# picotouch_grid.net
KiCad netlist of a schematic drawn in EAGLE
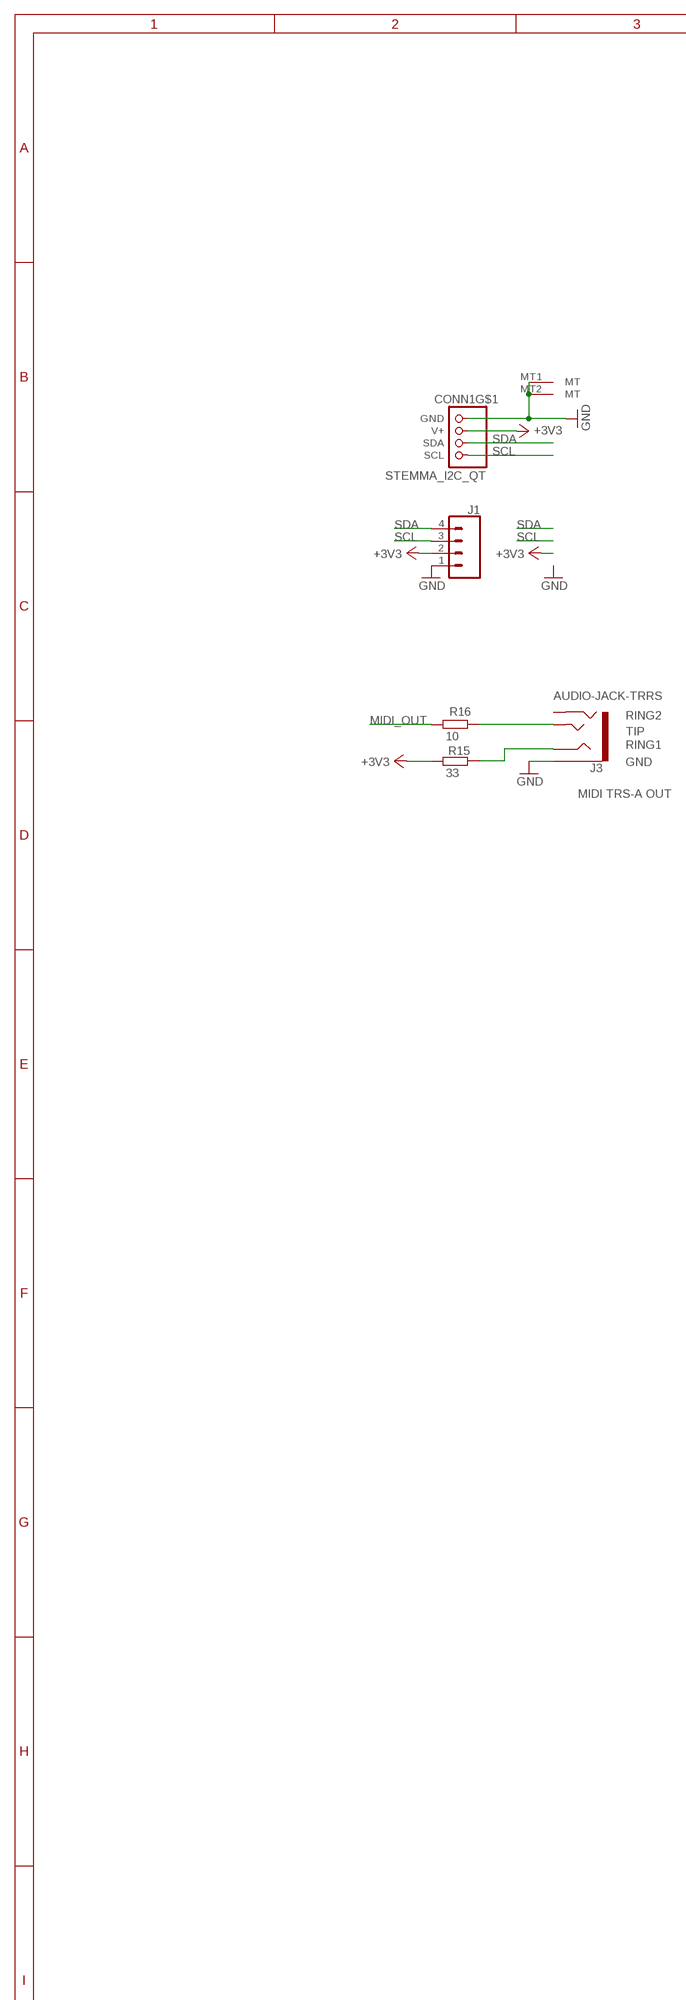
[diagram p0: schematic, sheet 1, part 1 of 2]
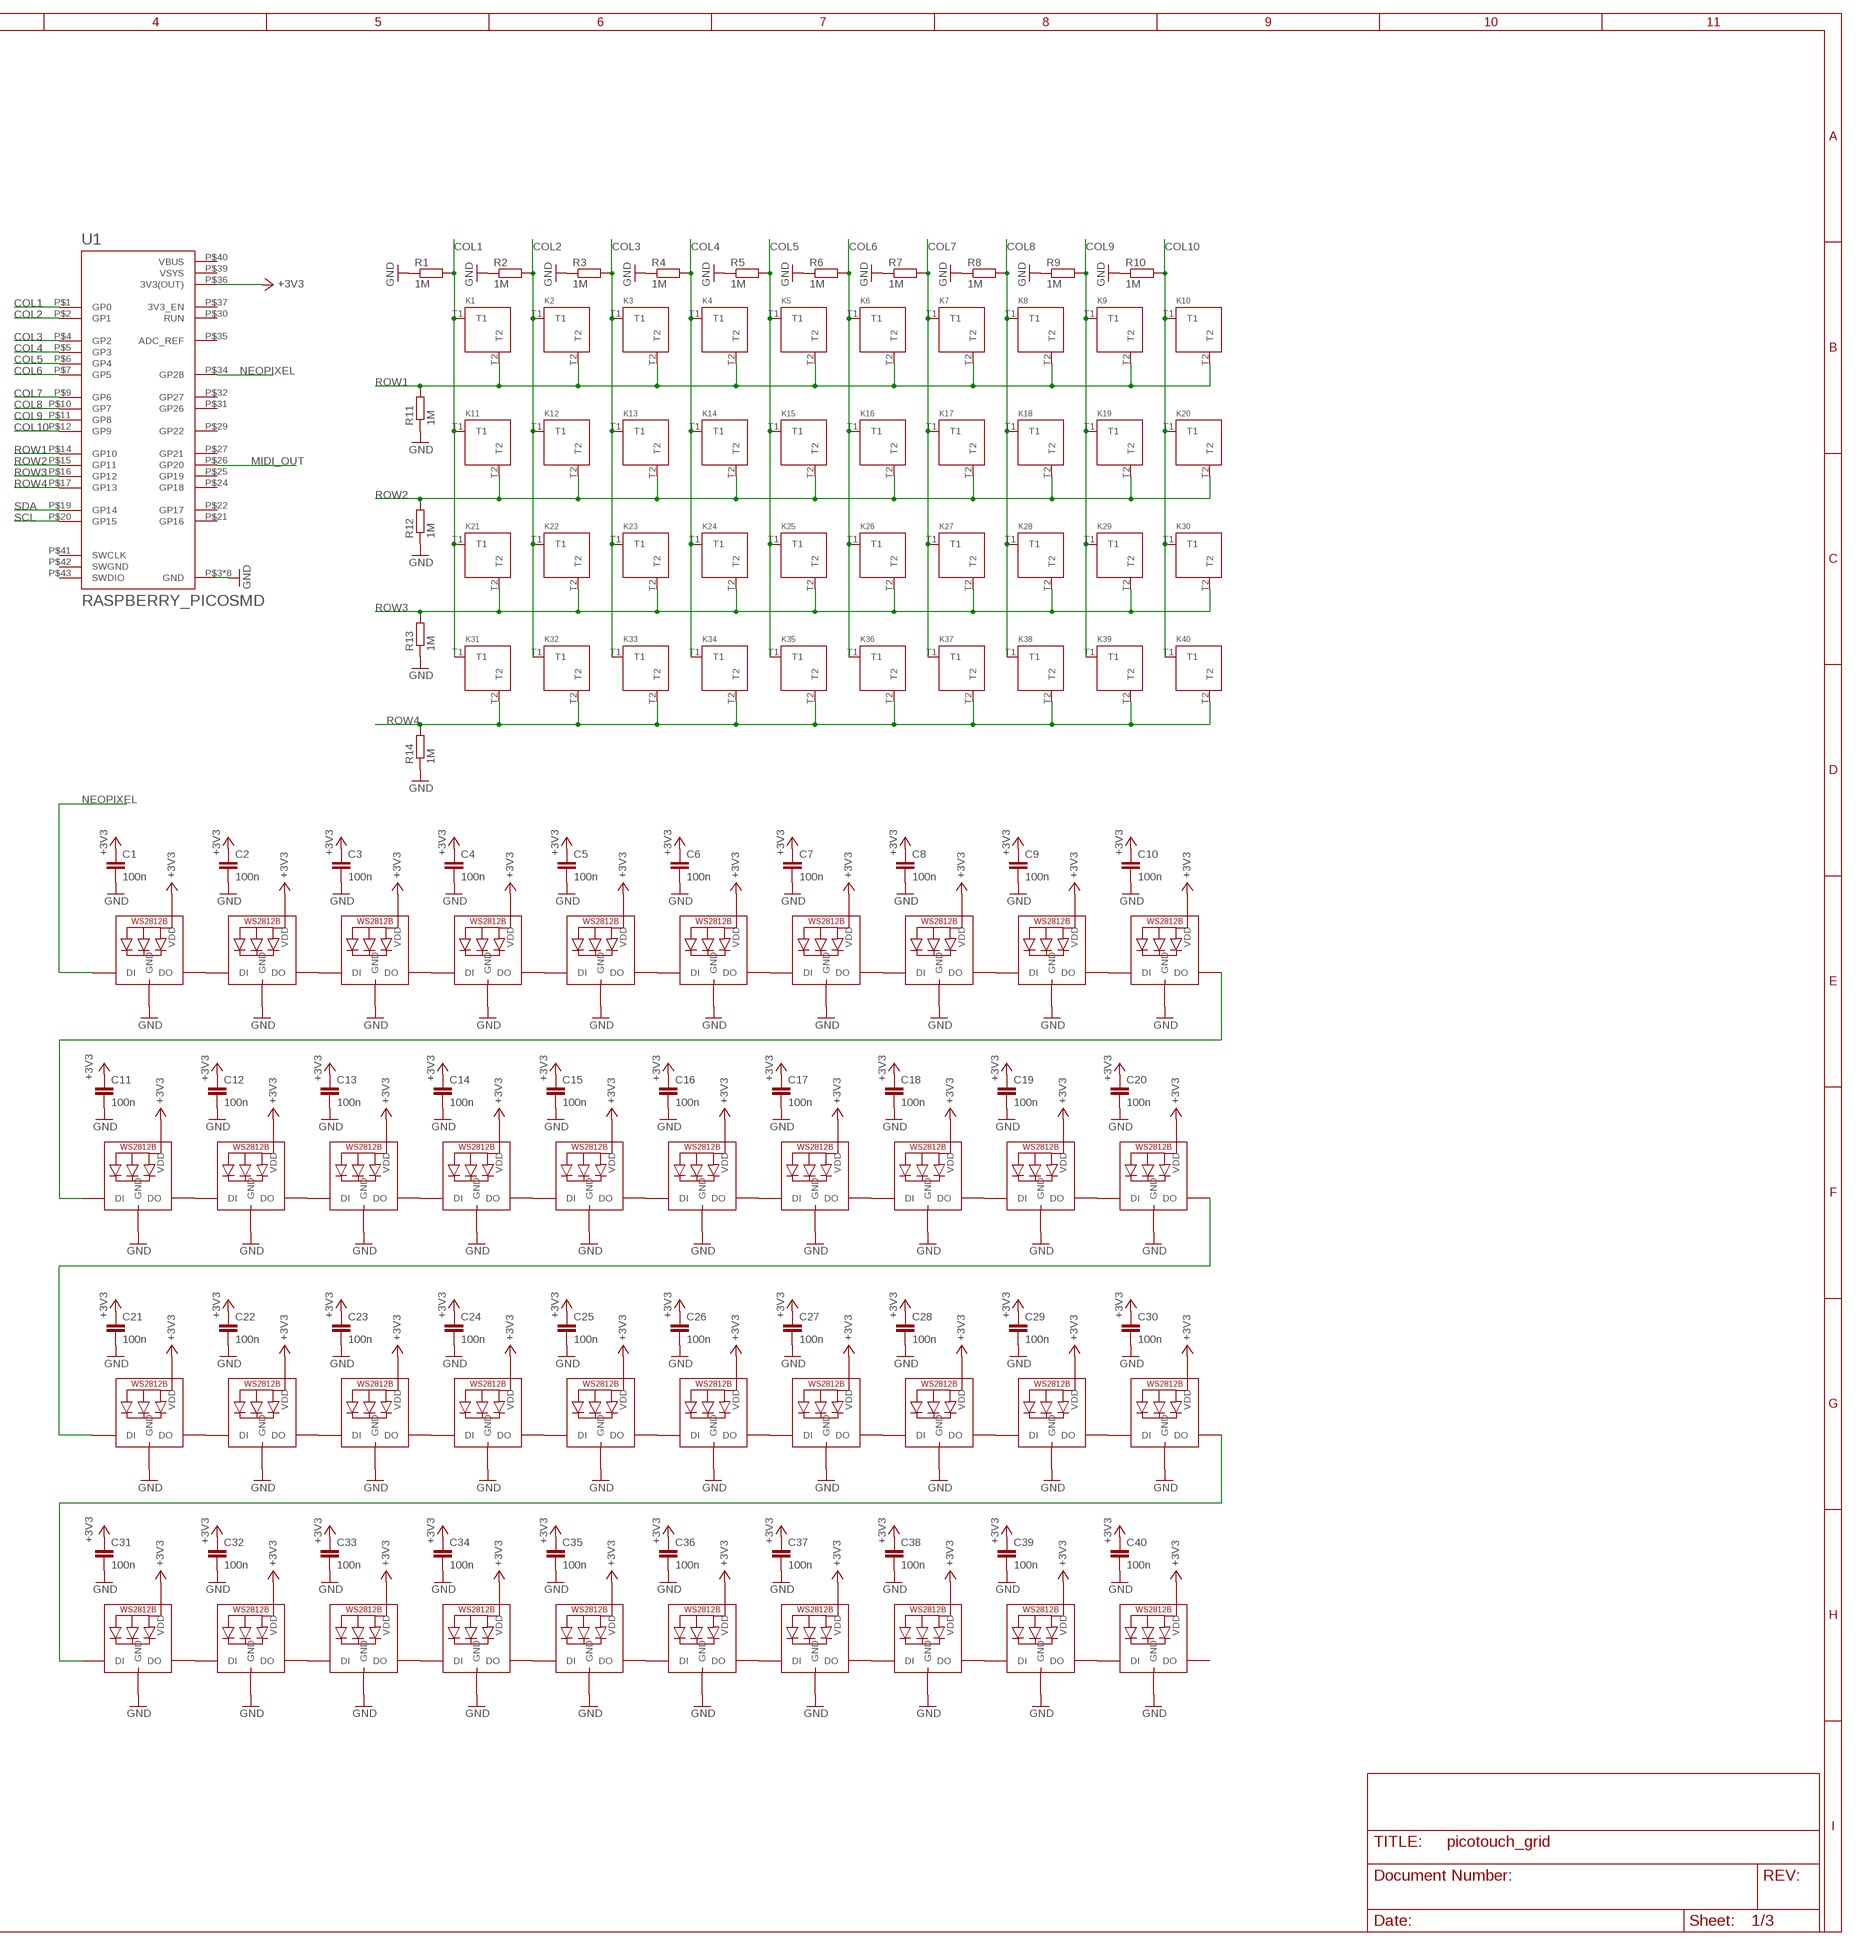
[diagram p1: schematic, sheet 1, part 2 of 2]

(export (version "E")
  (design (tool "Eeschema 10.0.6"))
  (components
    (comp (ref "C1")
      (value "100n")
      (footprint "eagle-import:C0805")
      (libsource (lib "eagle-import") (part "C-EUC0805"))
    )
    (comp (ref "C2")
      (value "100n")
      (footprint "eagle-import:C0805")
      (libsource (lib "eagle-import") (part "C-EUC0805"))
    )
    (comp (ref "C3")
      (value "100n")
      (footprint "eagle-import:C0805")
      (libsource (lib "eagle-import") (part "C-EUC0805"))
    )
    (comp (ref "C4")
      (value "100n")
      (footprint "eagle-import:C0805")
      (libsource (lib "eagle-import") (part "C-EUC0805"))
    )
    (comp (ref "C5")
      (value "100n")
      (footprint "eagle-import:C0805")
      (libsource (lib "eagle-import") (part "C-EUC0805"))
    )
    (comp (ref "C6")
      (value "100n")
      (footprint "eagle-import:C0805")
      (libsource (lib "eagle-import") (part "C-EUC0805"))
    )
    (comp (ref "C7")
      (value "100n")
      (footprint "eagle-import:C0805")
      (libsource (lib "eagle-import") (part "C-EUC0805"))
    )
    (comp (ref "C8")
      (value "100n")
      (footprint "eagle-import:C0805")
      (libsource (lib "eagle-import") (part "C-EUC0805"))
    )
    (comp (ref "C9")
      (value "100n")
      (footprint "eagle-import:C0805")
      (libsource (lib "eagle-import") (part "C-EUC0805"))
    )
    (comp (ref "C10")
      (value "100n")
      (footprint "eagle-import:C0805")
      (libsource (lib "eagle-import") (part "C-EUC0805"))
    )
    (comp (ref "C11")
      (value "100n")
      (footprint "eagle-import:C0805")
      (libsource (lib "eagle-import") (part "C-EUC0805"))
    )
    (comp (ref "C12")
      (value "100n")
      (footprint "eagle-import:C0805")
      (libsource (lib "eagle-import") (part "C-EUC0805"))
    )
    (comp (ref "C13")
      (value "100n")
      (footprint "eagle-import:C0805")
      (libsource (lib "eagle-import") (part "C-EUC0805"))
    )
    (comp (ref "C14")
      (value "100n")
      (footprint "eagle-import:C0805")
      (libsource (lib "eagle-import") (part "C-EUC0805"))
    )
    (comp (ref "C15")
      (value "100n")
      (footprint "eagle-import:C0805")
      (libsource (lib "eagle-import") (part "C-EUC0805"))
    )
    (comp (ref "C16")
      (value "100n")
      (footprint "eagle-import:C0805")
      (libsource (lib "eagle-import") (part "C-EUC0805"))
    )
    (comp (ref "C17")
      (value "100n")
      (footprint "eagle-import:C0805")
      (libsource (lib "eagle-import") (part "C-EUC0805"))
    )
    (comp (ref "C18")
      (value "100n")
      (footprint "eagle-import:C0805")
      (libsource (lib "eagle-import") (part "C-EUC0805"))
    )
    (comp (ref "C19")
      (value "100n")
      (footprint "eagle-import:C0805")
      (libsource (lib "eagle-import") (part "C-EUC0805"))
    )
    (comp (ref "C20")
      (value "100n")
      (footprint "eagle-import:C0805")
      (libsource (lib "eagle-import") (part "C-EUC0805"))
    )
    (comp (ref "C21")
      (value "100n")
      (footprint "eagle-import:C0805")
      (libsource (lib "eagle-import") (part "C-EUC0805"))
    )
    (comp (ref "C22")
      (value "100n")
      (footprint "eagle-import:C0805")
      (libsource (lib "eagle-import") (part "C-EUC0805"))
    )
    (comp (ref "C23")
      (value "100n")
      (footprint "eagle-import:C0805")
      (libsource (lib "eagle-import") (part "C-EUC0805"))
    )
    (comp (ref "C24")
      (value "100n")
      (footprint "eagle-import:C0805")
      (libsource (lib "eagle-import") (part "C-EUC0805"))
    )
    (comp (ref "C25")
      (value "100n")
      (footprint "eagle-import:C0805")
      (libsource (lib "eagle-import") (part "C-EUC0805"))
    )
    (comp (ref "C26")
      (value "100n")
      (footprint "eagle-import:C0805")
      (libsource (lib "eagle-import") (part "C-EUC0805"))
    )
    (comp (ref "C27")
      (value "100n")
      (footprint "eagle-import:C0805")
      (libsource (lib "eagle-import") (part "C-EUC0805"))
    )
    (comp (ref "C28")
      (value "100n")
      (footprint "eagle-import:C0805")
      (libsource (lib "eagle-import") (part "C-EUC0805"))
    )
    (comp (ref "C29")
      (value "100n")
      (footprint "eagle-import:C0805")
      (libsource (lib "eagle-import") (part "C-EUC0805"))
    )
    (comp (ref "C30")
      (value "100n")
      (footprint "eagle-import:C0805")
      (libsource (lib "eagle-import") (part "C-EUC0805"))
    )
    (comp (ref "C31")
      (value "100n")
      (footprint "eagle-import:C0805")
      (libsource (lib "eagle-import") (part "C-EUC0805"))
    )
    (comp (ref "C32")
      (value "100n")
      (footprint "eagle-import:C0805")
      (libsource (lib "eagle-import") (part "C-EUC0805"))
    )
    (comp (ref "C33")
      (value "100n")
      (footprint "eagle-import:C0805")
      (libsource (lib "eagle-import") (part "C-EUC0805"))
    )
    (comp (ref "C34")
      (value "100n")
      (footprint "eagle-import:C0805")
      (libsource (lib "eagle-import") (part "C-EUC0805"))
    )
    (comp (ref "C35")
      (value "100n")
      (footprint "eagle-import:C0805")
      (libsource (lib "eagle-import") (part "C-EUC0805"))
    )
    (comp (ref "C36")
      (value "100n")
      (footprint "eagle-import:C0805")
      (libsource (lib "eagle-import") (part "C-EUC0805"))
    )
    (comp (ref "C37")
      (value "100n")
      (footprint "eagle-import:C0805")
      (libsource (lib "eagle-import") (part "C-EUC0805"))
    )
    (comp (ref "C38")
      (value "100n")
      (footprint "eagle-import:C0805")
      (libsource (lib "eagle-import") (part "C-EUC0805"))
    )
    (comp (ref "C39")
      (value "100n")
      (footprint "eagle-import:C0805")
      (libsource (lib "eagle-import") (part "C-EUC0805"))
    )
    (comp (ref "C40")
      (value "100n")
      (footprint "eagle-import:C0805")
      (libsource (lib "eagle-import") (part "C-EUC0805"))
    )
    (comp (ref "CONN1")
      (value "STEMMA_I2C_QT")
      (footprint "eagle-import:JST_SH4")
      (fields
        (field (name "LCSC2") "C160404")
        (field (name "MPN") "HC-1.0-4PWT")
        (field (name "MPN2") "SM04B-SRSS-TB")
      )
      (libsource (lib "eagle-import") (part "STEMMA_I2C_QT"))
    )
    (comp (ref "J1")
      (value "CONN_04")
      (footprint "eagle-import:1X04")
      (libsource (lib "eagle-import") (part "CONN_04"))
    )
    (comp (ref "J3")
      (value "AUDIO-JACK-TRRS")
      (footprint "eagle-import:PJ-320D_SPARKFUN")
      (fields (field (name "MPN") "PJ-320D") (field (name "LCSC") "C431535"))
      (libsource (lib "eagle-import") (part "AUDIO-JACK-TRRS"))
    )
    (comp (ref "K1")
      (value "TOUCHKEYH")
      (footprint "eagle-import:TOUCHPAD_KEY_0.5IN_LEDHOLE")
      (libsource (lib "eagle-import") (part "TOUCHKEYH"))
    )
    (comp (ref "K2")
      (value "TOUCHKEYH")
      (footprint "eagle-import:TOUCHPAD_KEY_0.5IN_LEDHOLE")
      (libsource (lib "eagle-import") (part "TOUCHKEYH"))
    )
    (comp (ref "K3")
      (value "TOUCHKEYH")
      (footprint "eagle-import:TOUCHPAD_KEY_0.5IN_LEDHOLE")
      (libsource (lib "eagle-import") (part "TOUCHKEYH"))
    )
    (comp (ref "K4")
      (value "TOUCHKEYH")
      (footprint "eagle-import:TOUCHPAD_KEY_0.5IN_LEDHOLE")
      (libsource (lib "eagle-import") (part "TOUCHKEYH"))
    )
    (comp (ref "K5")
      (value "TOUCHKEYH")
      (footprint "eagle-import:TOUCHPAD_KEY_0.5IN_LEDHOLE")
      (libsource (lib "eagle-import") (part "TOUCHKEYH"))
    )
    (comp (ref "K6")
      (value "TOUCHKEYH")
      (footprint "eagle-import:TOUCHPAD_KEY_0.5IN_LEDHOLE")
      (libsource (lib "eagle-import") (part "TOUCHKEYH"))
    )
    (comp (ref "K7")
      (value "TOUCHKEYH")
      (footprint "eagle-import:TOUCHPAD_KEY_0.5IN_LEDHOLE")
      (libsource (lib "eagle-import") (part "TOUCHKEYH"))
    )
    (comp (ref "K8")
      (value "TOUCHKEYH")
      (footprint "eagle-import:TOUCHPAD_KEY_0.5IN_LEDHOLE")
      (libsource (lib "eagle-import") (part "TOUCHKEYH"))
    )
    (comp (ref "K9")
      (value "TOUCHKEYH")
      (footprint "eagle-import:TOUCHPAD_KEY_0.5IN_LEDHOLE")
      (libsource (lib "eagle-import") (part "TOUCHKEYH"))
    )
    (comp (ref "K10")
      (value "TOUCHKEYH")
      (footprint "eagle-import:TOUCHPAD_KEY_0.5IN_LEDHOLE")
      (libsource (lib "eagle-import") (part "TOUCHKEYH"))
    )
    (comp (ref "K11")
      (value "TOUCHKEYH")
      (footprint "eagle-import:TOUCHPAD_KEY_0.5IN_LEDHOLE")
      (libsource (lib "eagle-import") (part "TOUCHKEYH"))
    )
    (comp (ref "K12")
      (value "TOUCHKEYH")
      (footprint "eagle-import:TOUCHPAD_KEY_0.5IN_LEDHOLE")
      (libsource (lib "eagle-import") (part "TOUCHKEYH"))
    )
    (comp (ref "K13")
      (value "TOUCHKEYH")
      (footprint "eagle-import:TOUCHPAD_KEY_0.5IN_LEDHOLE")
      (libsource (lib "eagle-import") (part "TOUCHKEYH"))
    )
    (comp (ref "K14")
      (value "TOUCHKEYH")
      (footprint "eagle-import:TOUCHPAD_KEY_0.5IN_LEDHOLE")
      (libsource (lib "eagle-import") (part "TOUCHKEYH"))
    )
    (comp (ref "K15")
      (value "TOUCHKEYH")
      (footprint "eagle-import:TOUCHPAD_KEY_0.5IN_LEDHOLE")
      (libsource (lib "eagle-import") (part "TOUCHKEYH"))
    )
    (comp (ref "K16")
      (value "TOUCHKEYH")
      (footprint "eagle-import:TOUCHPAD_KEY_0.5IN_LEDHOLE")
      (libsource (lib "eagle-import") (part "TOUCHKEYH"))
    )
    (comp (ref "K17")
      (value "TOUCHKEYH")
      (footprint "eagle-import:TOUCHPAD_KEY_0.5IN_LEDHOLE")
      (libsource (lib "eagle-import") (part "TOUCHKEYH"))
    )
    (comp (ref "K18")
      (value "TOUCHKEYH")
      (footprint "eagle-import:TOUCHPAD_KEY_0.5IN_LEDHOLE")
      (libsource (lib "eagle-import") (part "TOUCHKEYH"))
    )
    (comp (ref "K19")
      (value "TOUCHKEYH")
      (footprint "eagle-import:TOUCHPAD_KEY_0.5IN_LEDHOLE")
      (libsource (lib "eagle-import") (part "TOUCHKEYH"))
    )
    (comp (ref "K20")
      (value "TOUCHKEYH")
      (footprint "eagle-import:TOUCHPAD_KEY_0.5IN_LEDHOLE")
      (libsource (lib "eagle-import") (part "TOUCHKEYH"))
    )
    (comp (ref "K21")
      (value "TOUCHKEYH")
      (footprint "eagle-import:TOUCHPAD_KEY_0.5IN_LEDHOLE")
      (libsource (lib "eagle-import") (part "TOUCHKEYH"))
    )
    (comp (ref "K22")
      (value "TOUCHKEYH")
      (footprint "eagle-import:TOUCHPAD_KEY_0.5IN_LEDHOLE")
      (libsource (lib "eagle-import") (part "TOUCHKEYH"))
    )
    (comp (ref "K23")
      (value "TOUCHKEYH")
      (footprint "eagle-import:TOUCHPAD_KEY_0.5IN_LEDHOLE")
      (libsource (lib "eagle-import") (part "TOUCHKEYH"))
    )
    (comp (ref "K24")
      (value "TOUCHKEYH")
      (footprint "eagle-import:TOUCHPAD_KEY_0.5IN_LEDHOLE")
      (libsource (lib "eagle-import") (part "TOUCHKEYH"))
    )
    (comp (ref "K25")
      (value "TOUCHKEYH")
      (footprint "eagle-import:TOUCHPAD_KEY_0.5IN_LEDHOLE")
      (libsource (lib "eagle-import") (part "TOUCHKEYH"))
    )
    (comp (ref "K26")
      (value "TOUCHKEYH")
      (footprint "eagle-import:TOUCHPAD_KEY_0.5IN_LEDHOLE")
      (libsource (lib "eagle-import") (part "TOUCHKEYH"))
    )
    (comp (ref "K27")
      (value "TOUCHKEYH")
      (footprint "eagle-import:TOUCHPAD_KEY_0.5IN_LEDHOLE")
      (libsource (lib "eagle-import") (part "TOUCHKEYH"))
    )
    (comp (ref "K28")
      (value "TOUCHKEYH")
      (footprint "eagle-import:TOUCHPAD_KEY_0.5IN_LEDHOLE")
      (libsource (lib "eagle-import") (part "TOUCHKEYH"))
    )
    (comp (ref "K29")
      (value "TOUCHKEYH")
      (footprint "eagle-import:TOUCHPAD_KEY_0.5IN_LEDHOLE")
      (libsource (lib "eagle-import") (part "TOUCHKEYH"))
    )
    (comp (ref "K30")
      (value "TOUCHKEYH")
      (footprint "eagle-import:TOUCHPAD_KEY_0.5IN_LEDHOLE")
      (libsource (lib "eagle-import") (part "TOUCHKEYH"))
    )
    (comp (ref "K31")
      (value "TOUCHKEYH")
      (footprint "eagle-import:TOUCHPAD_KEY_0.5IN_LEDHOLE")
      (libsource (lib "eagle-import") (part "TOUCHKEYH"))
    )
    (comp (ref "K32")
      (value "TOUCHKEYH")
      (footprint "eagle-import:TOUCHPAD_KEY_0.5IN_LEDHOLE")
      (libsource (lib "eagle-import") (part "TOUCHKEYH"))
    )
    (comp (ref "K33")
      (value "TOUCHKEYH")
      (footprint "eagle-import:TOUCHPAD_KEY_0.5IN_LEDHOLE")
      (libsource (lib "eagle-import") (part "TOUCHKEYH"))
    )
    (comp (ref "K34")
      (value "TOUCHKEYH")
      (footprint "eagle-import:TOUCHPAD_KEY_0.5IN_LEDHOLE")
      (libsource (lib "eagle-import") (part "TOUCHKEYH"))
    )
    (comp (ref "K35")
      (value "TOUCHKEYH")
      (footprint "eagle-import:TOUCHPAD_KEY_0.5IN_LEDHOLE")
      (libsource (lib "eagle-import") (part "TOUCHKEYH"))
    )
    (comp (ref "K36")
      (value "TOUCHKEYH")
      (footprint "eagle-import:TOUCHPAD_KEY_0.5IN_LEDHOLE")
      (libsource (lib "eagle-import") (part "TOUCHKEYH"))
    )
    (comp (ref "K37")
      (value "TOUCHKEYH")
      (footprint "eagle-import:TOUCHPAD_KEY_0.5IN_LEDHOLE")
      (libsource (lib "eagle-import") (part "TOUCHKEYH"))
    )
    (comp (ref "K38")
      (value "TOUCHKEYH")
      (footprint "eagle-import:TOUCHPAD_KEY_0.5IN_LEDHOLE")
      (libsource (lib "eagle-import") (part "TOUCHKEYH"))
    )
    (comp (ref "K39")
      (value "TOUCHKEYH")
      (footprint "eagle-import:TOUCHPAD_KEY_0.5IN_LEDHOLE")
      (libsource (lib "eagle-import") (part "TOUCHKEYH"))
    )
    (comp (ref "K40")
      (value "TOUCHKEYH")
      (footprint "eagle-import:TOUCHPAD_KEY_0.5IN_LEDHOLE")
      (libsource (lib "eagle-import") (part "TOUCHKEYH"))
    )
    (comp (ref "LED1")
      (value "MICROBUILDER_WS2812B_SK6812E")
      (footprint "eagle-import:MICROBUILDER_NEO3535_REVERSE")
      (libsource (lib "eagle-import") (part "MICROBUILDER_WS2812B_SK6812E"))
    )
    (comp (ref "LED2")
      (value "MICROBUILDER_WS2812B_SK6812E")
      (footprint "eagle-import:MICROBUILDER_NEO3535_REVERSE")
      (libsource (lib "eagle-import") (part "MICROBUILDER_WS2812B_SK6812E"))
    )
    (comp (ref "LED3")
      (value "MICROBUILDER_WS2812B_SK6812E")
      (footprint "eagle-import:MICROBUILDER_NEO3535_REVERSE")
      (libsource (lib "eagle-import") (part "MICROBUILDER_WS2812B_SK6812E"))
    )
    (comp (ref "LED4")
      (value "MICROBUILDER_WS2812B_SK6812E")
      (footprint "eagle-import:MICROBUILDER_NEO3535_REVERSE")
      (libsource (lib "eagle-import") (part "MICROBUILDER_WS2812B_SK6812E"))
    )
    (comp (ref "LED5")
      (value "MICROBUILDER_WS2812B_SK6812E")
      (footprint "eagle-import:MICROBUILDER_NEO3535_REVERSE")
      (libsource (lib "eagle-import") (part "MICROBUILDER_WS2812B_SK6812E"))
    )
    (comp (ref "LED6")
      (value "MICROBUILDER_WS2812B_SK6812E")
      (footprint "eagle-import:MICROBUILDER_NEO3535_REVERSE")
      (libsource (lib "eagle-import") (part "MICROBUILDER_WS2812B_SK6812E"))
    )
    (comp (ref "LED7")
      (value "MICROBUILDER_WS2812B_SK6812E")
      (footprint "eagle-import:MICROBUILDER_NEO3535_REVERSE")
      (libsource (lib "eagle-import") (part "MICROBUILDER_WS2812B_SK6812E"))
    )
    (comp (ref "LED8")
      (value "MICROBUILDER_WS2812B_SK6812E")
      (footprint "eagle-import:MICROBUILDER_NEO3535_REVERSE")
      (libsource (lib "eagle-import") (part "MICROBUILDER_WS2812B_SK6812E"))
    )
    (comp (ref "LED9")
      (value "MICROBUILDER_WS2812B_SK6812E")
      (footprint "eagle-import:MICROBUILDER_NEO3535_REVERSE")
      (libsource (lib "eagle-import") (part "MICROBUILDER_WS2812B_SK6812E"))
    )
    (comp (ref "LED10")
      (value "MICROBUILDER_WS2812B_SK6812E")
      (footprint "eagle-import:MICROBUILDER_NEO3535_REVERSE")
      (libsource (lib "eagle-import") (part "MICROBUILDER_WS2812B_SK6812E"))
    )
    (comp (ref "LED11")
      (value "MICROBUILDER_WS2812B_SK6812E")
      (footprint "eagle-import:MICROBUILDER_NEO3535_REVERSE")
      (libsource (lib "eagle-import") (part "MICROBUILDER_WS2812B_SK6812E"))
    )
    (comp (ref "LED12")
      (value "MICROBUILDER_WS2812B_SK6812E")
      (footprint "eagle-import:MICROBUILDER_NEO3535_REVERSE")
      (libsource (lib "eagle-import") (part "MICROBUILDER_WS2812B_SK6812E"))
    )
    (comp (ref "LED13")
      (value "MICROBUILDER_WS2812B_SK6812E")
      (footprint "eagle-import:MICROBUILDER_NEO3535_REVERSE")
      (libsource (lib "eagle-import") (part "MICROBUILDER_WS2812B_SK6812E"))
    )
    (comp (ref "LED14")
      (value "MICROBUILDER_WS2812B_SK6812E")
      (footprint "eagle-import:MICROBUILDER_NEO3535_REVERSE")
      (libsource (lib "eagle-import") (part "MICROBUILDER_WS2812B_SK6812E"))
    )
    (comp (ref "LED15")
      (value "MICROBUILDER_WS2812B_SK6812E")
      (footprint "eagle-import:MICROBUILDER_NEO3535_REVERSE")
      (libsource (lib "eagle-import") (part "MICROBUILDER_WS2812B_SK6812E"))
    )
    (comp (ref "LED16")
      (value "MICROBUILDER_WS2812B_SK6812E")
      (footprint "eagle-import:MICROBUILDER_NEO3535_REVERSE")
      (libsource (lib "eagle-import") (part "MICROBUILDER_WS2812B_SK6812E"))
    )
    (comp (ref "LED17")
      (value "MICROBUILDER_WS2812B_SK6812E")
      (footprint "eagle-import:MICROBUILDER_NEO3535_REVERSE")
      (libsource (lib "eagle-import") (part "MICROBUILDER_WS2812B_SK6812E"))
    )
    (comp (ref "LED18")
      (value "MICROBUILDER_WS2812B_SK6812E")
      (footprint "eagle-import:MICROBUILDER_NEO3535_REVERSE")
      (libsource (lib "eagle-import") (part "MICROBUILDER_WS2812B_SK6812E"))
    )
    (comp (ref "LED19")
      (value "MICROBUILDER_WS2812B_SK6812E")
      (footprint "eagle-import:MICROBUILDER_NEO3535_REVERSE")
      (libsource (lib "eagle-import") (part "MICROBUILDER_WS2812B_SK6812E"))
    )
    (comp (ref "LED20")
      (value "MICROBUILDER_WS2812B_SK6812E")
      (footprint "eagle-import:MICROBUILDER_NEO3535_REVERSE")
      (libsource (lib "eagle-import") (part "MICROBUILDER_WS2812B_SK6812E"))
    )
    (comp (ref "LED21")
      (value "MICROBUILDER_WS2812B_SK6812E")
      (footprint "eagle-import:MICROBUILDER_NEO3535_REVERSE")
      (libsource (lib "eagle-import") (part "MICROBUILDER_WS2812B_SK6812E"))
    )
    (comp (ref "LED22")
      (value "MICROBUILDER_WS2812B_SK6812E")
      (footprint "eagle-import:MICROBUILDER_NEO3535_REVERSE")
      (libsource (lib "eagle-import") (part "MICROBUILDER_WS2812B_SK6812E"))
    )
    (comp (ref "LED23")
      (value "MICROBUILDER_WS2812B_SK6812E")
      (footprint "eagle-import:MICROBUILDER_NEO3535_REVERSE")
      (libsource (lib "eagle-import") (part "MICROBUILDER_WS2812B_SK6812E"))
    )
    (comp (ref "LED24")
      (value "MICROBUILDER_WS2812B_SK6812E")
      (footprint "eagle-import:MICROBUILDER_NEO3535_REVERSE")
      (libsource (lib "eagle-import") (part "MICROBUILDER_WS2812B_SK6812E"))
    )
    (comp (ref "LED25")
      (value "MICROBUILDER_WS2812B_SK6812E")
      (footprint "eagle-import:MICROBUILDER_NEO3535_REVERSE")
      (libsource (lib "eagle-import") (part "MICROBUILDER_WS2812B_SK6812E"))
    )
    (comp (ref "LED26")
      (value "MICROBUILDER_WS2812B_SK6812E")
      (footprint "eagle-import:MICROBUILDER_NEO3535_REVERSE")
      (libsource (lib "eagle-import") (part "MICROBUILDER_WS2812B_SK6812E"))
    )
    (comp (ref "LED27")
      (value "MICROBUILDER_WS2812B_SK6812E")
      (footprint "eagle-import:MICROBUILDER_NEO3535_REVERSE")
      (libsource (lib "eagle-import") (part "MICROBUILDER_WS2812B_SK6812E"))
    )
    (comp (ref "LED28")
      (value "MICROBUILDER_WS2812B_SK6812E")
      (footprint "eagle-import:MICROBUILDER_NEO3535_REVERSE")
      (libsource (lib "eagle-import") (part "MICROBUILDER_WS2812B_SK6812E"))
    )
    (comp (ref "LED29")
      (value "MICROBUILDER_WS2812B_SK6812E")
      (footprint "eagle-import:MICROBUILDER_NEO3535_REVERSE")
      (libsource (lib "eagle-import") (part "MICROBUILDER_WS2812B_SK6812E"))
    )
    (comp (ref "LED30")
      (value "MICROBUILDER_WS2812B_SK6812E")
      (footprint "eagle-import:MICROBUILDER_NEO3535_REVERSE")
      (libsource (lib "eagle-import") (part "MICROBUILDER_WS2812B_SK6812E"))
    )
    (comp (ref "LED31")
      (value "MICROBUILDER_WS2812B_SK6812E")
      (footprint "eagle-import:MICROBUILDER_NEO3535_REVERSE")
      (libsource (lib "eagle-import") (part "MICROBUILDER_WS2812B_SK6812E"))
    )
    (comp (ref "LED32")
      (value "MICROBUILDER_WS2812B_SK6812E")
      (footprint "eagle-import:MICROBUILDER_NEO3535_REVERSE")
      (libsource (lib "eagle-import") (part "MICROBUILDER_WS2812B_SK6812E"))
    )
    (comp (ref "LED33")
      (value "MICROBUILDER_WS2812B_SK6812E")
      (footprint "eagle-import:MICROBUILDER_NEO3535_REVERSE")
      (libsource (lib "eagle-import") (part "MICROBUILDER_WS2812B_SK6812E"))
    )
    (comp (ref "LED34")
      (value "MICROBUILDER_WS2812B_SK6812E")
      (footprint "eagle-import:MICROBUILDER_NEO3535_REVERSE")
      (libsource (lib "eagle-import") (part "MICROBUILDER_WS2812B_SK6812E"))
    )
    (comp (ref "LED35")
      (value "MICROBUILDER_WS2812B_SK6812E")
      (footprint "eagle-import:MICROBUILDER_NEO3535_REVERSE")
      (libsource (lib "eagle-import") (part "MICROBUILDER_WS2812B_SK6812E"))
    )
    (comp (ref "LED36")
      (value "MICROBUILDER_WS2812B_SK6812E")
      (footprint "eagle-import:MICROBUILDER_NEO3535_REVERSE")
      (libsource (lib "eagle-import") (part "MICROBUILDER_WS2812B_SK6812E"))
    )
    (comp (ref "LED37")
      (value "MICROBUILDER_WS2812B_SK6812E")
      (footprint "eagle-import:MICROBUILDER_NEO3535_REVERSE")
      (libsource (lib "eagle-import") (part "MICROBUILDER_WS2812B_SK6812E"))
    )
    (comp (ref "LED38")
      (value "MICROBUILDER_WS2812B_SK6812E")
      (footprint "eagle-import:MICROBUILDER_NEO3535_REVERSE")
      (libsource (lib "eagle-import") (part "MICROBUILDER_WS2812B_SK6812E"))
    )
    (comp (ref "LED39")
      (value "MICROBUILDER_WS2812B_SK6812E")
      (footprint "eagle-import:MICROBUILDER_NEO3535_REVERSE")
      (libsource (lib "eagle-import") (part "MICROBUILDER_WS2812B_SK6812E"))
    )
    (comp (ref "LED40")
      (value "MICROBUILDER_WS2812B_SK6812E")
      (footprint "eagle-import:MICROBUILDER_NEO3535_REVERSE")
      (libsource (lib "eagle-import") (part "MICROBUILDER_WS2812B_SK6812E"))
    )
    (comp (ref "R1")
      (value "1M")
      (footprint "eagle-import:R0805")
      (libsource (lib "eagle-import") (part "R-EU_R0805"))
    )
    (comp (ref "R2")
      (value "1M")
      (footprint "eagle-import:R0805")
      (libsource (lib "eagle-import") (part "R-EU_R0805"))
    )
    (comp (ref "R3")
      (value "1M")
      (footprint "eagle-import:R0805")
      (libsource (lib "eagle-import") (part "R-EU_R0805"))
    )
    (comp (ref "R4")
      (value "1M")
      (footprint "eagle-import:R0805")
      (libsource (lib "eagle-import") (part "R-EU_R0805"))
    )
    (comp (ref "R5")
      (value "1M")
      (footprint "eagle-import:R0805")
      (libsource (lib "eagle-import") (part "R-EU_R0805"))
    )
    (comp (ref "R6")
      (value "1M")
      (footprint "eagle-import:R0805")
      (libsource (lib "eagle-import") (part "R-EU_R0805"))
    )
    (comp (ref "R7")
      (value "1M")
      (footprint "eagle-import:R0805")
      (libsource (lib "eagle-import") (part "R-EU_R0805"))
    )
    (comp (ref "R8")
      (value "1M")
      (footprint "eagle-import:R0805")
      (libsource (lib "eagle-import") (part "R-EU_R0805"))
    )
    (comp (ref "R9")
      (value "1M")
      (footprint "eagle-import:R0805")
      (libsource (lib "eagle-import") (part "R-EU_R0805"))
    )
    (comp (ref "R10")
      (value "1M")
      (footprint "eagle-import:R0805")
      (libsource (lib "eagle-import") (part "R-EU_R0805"))
    )
    (comp (ref "R11")
      (value "1M")
      (footprint "eagle-import:R0805")
      (libsource (lib "eagle-import") (part "R-EU_R0805"))
    )
    (comp (ref "R12")
      (value "1M")
      (footprint "eagle-import:R0805")
      (libsource (lib "eagle-import") (part "R-EU_R0805"))
    )
    (comp (ref "R13")
      (value "1M")
      (footprint "eagle-import:R0805")
      (libsource (lib "eagle-import") (part "R-EU_R0805"))
    )
    (comp (ref "R14")
      (value "1M")
      (footprint "eagle-import:R0805")
      (libsource (lib "eagle-import") (part "R-EU_R0805"))
    )
    (comp (ref "R15")
      (value "33")
      (footprint "eagle-import:R0805")
      (libsource (lib "eagle-import") (part "R-EU_R0805"))
    )
    (comp (ref "R16")
      (value "10")
      (footprint "eagle-import:R0805")
      (libsource (lib "eagle-import") (part "R-EU_R0805"))
    )
    (comp (ref "U1")
      (value "RASPBERRY_PICOSMD")
      (footprint "eagle-import:PICO-PKG-SMD")
      (libsource (lib "eagle-import") (part "RASPBERRY_PICOSMD"))
    )
  )
  (nets
    (net (code "1") (name "+3V3") (class "Default")
      (node (ref "C1") (pin "1") (pinfunction "1_1") (pintype "passive"))
      (node (ref "C10") (pin "1") (pinfunction "1_1") (pintype "passive"))
      (node (ref "C11") (pin "1") (pinfunction "1_1") (pintype "passive"))
      (node (ref "C12") (pin "1") (pinfunction "1_1") (pintype "passive"))
      (node (ref "C13") (pin "1") (pinfunction "1_1") (pintype "passive"))
      (node (ref "C14") (pin "1") (pinfunction "1_1") (pintype "passive"))
      (node (ref "C15") (pin "1") (pinfunction "1_1") (pintype "passive"))
      (node (ref "C16") (pin "1") (pinfunction "1_1") (pintype "passive"))
      (node (ref "C17") (pin "1") (pinfunction "1_1") (pintype "passive"))
      (node (ref "C18") (pin "1") (pinfunction "1_1") (pintype "passive"))
      (node (ref "C19") (pin "1") (pinfunction "1_1") (pintype "passive"))
      (node (ref "C2") (pin "1") (pinfunction "1_1") (pintype "passive"))
      (node (ref "C20") (pin "1") (pinfunction "1_1") (pintype "passive"))
      (node (ref "C21") (pin "1") (pinfunction "1_1") (pintype "passive"))
      (node (ref "C22") (pin "1") (pinfunction "1_1") (pintype "passive"))
      (node (ref "C23") (pin "1") (pinfunction "1_1") (pintype "passive"))
      (node (ref "C24") (pin "1") (pinfunction "1_1") (pintype "passive"))
      (node (ref "C25") (pin "1") (pinfunction "1_1") (pintype "passive"))
      (node (ref "C26") (pin "1") (pinfunction "1_1") (pintype "passive"))
      (node (ref "C27") (pin "1") (pinfunction "1_1") (pintype "passive"))
      (node (ref "C28") (pin "1") (pinfunction "1_1") (pintype "passive"))
      (node (ref "C29") (pin "1") (pinfunction "1_1") (pintype "passive"))
      (node (ref "C3") (pin "1") (pinfunction "1_1") (pintype "passive"))
      (node (ref "C30") (pin "1") (pinfunction "1_1") (pintype "passive"))
      (node (ref "C31") (pin "1") (pinfunction "1_1") (pintype "passive"))
      (node (ref "C32") (pin "1") (pinfunction "1_1") (pintype "passive"))
      (node (ref "C33") (pin "1") (pinfunction "1_1") (pintype "passive"))
      (node (ref "C34") (pin "1") (pinfunction "1_1") (pintype "passive"))
      (node (ref "C35") (pin "1") (pinfunction "1_1") (pintype "passive"))
      (node (ref "C36") (pin "1") (pinfunction "1_1") (pintype "passive"))
      (node (ref "C37") (pin "1") (pinfunction "1_1") (pintype "passive"))
      (node (ref "C38") (pin "1") (pinfunction "1_1") (pintype "passive"))
      (node (ref "C39") (pin "1") (pinfunction "1_1") (pintype "passive"))
      (node (ref "C4") (pin "1") (pinfunction "1_1") (pintype "passive"))
      (node (ref "C40") (pin "1") (pinfunction "1_1") (pintype "passive"))
      (node (ref "C5") (pin "1") (pinfunction "1_1") (pintype "passive"))
      (node (ref "C6") (pin "1") (pinfunction "1_1") (pintype "passive"))
      (node (ref "C7") (pin "1") (pinfunction "1_1") (pintype "passive"))
      (node (ref "C8") (pin "1") (pinfunction "1_1") (pintype "passive"))
      (node (ref "C9") (pin "1") (pinfunction "1_1") (pintype "passive"))
      (node (ref "CONN1") (pin "2") (pinfunction "V+_2") (pintype "passive"))
      (node (ref "J1") (pin "2") (pinfunction "2_2") (pintype "passive"))
      (node (ref "LED1") (pin "1-VDD") (pinfunction "VDD_1-VDD") (pintype "power_in"))
      (node (ref "LED10") (pin "1-VDD") (pinfunction "VDD_1-VDD") (pintype "power_in"))
      (node (ref "LED11") (pin "1-VDD") (pinfunction "VDD_1-VDD") (pintype "power_in"))
      (node (ref "LED12") (pin "1-VDD") (pinfunction "VDD_1-VDD") (pintype "power_in"))
      (node (ref "LED13") (pin "1-VDD") (pinfunction "VDD_1-VDD") (pintype "power_in"))
      (node (ref "LED14") (pin "1-VDD") (pinfunction "VDD_1-VDD") (pintype "power_in"))
      (node (ref "LED15") (pin "1-VDD") (pinfunction "VDD_1-VDD") (pintype "power_in"))
      (node (ref "LED16") (pin "1-VDD") (pinfunction "VDD_1-VDD") (pintype "power_in"))
      (node (ref "LED17") (pin "1-VDD") (pinfunction "VDD_1-VDD") (pintype "power_in"))
      (node (ref "LED18") (pin "1-VDD") (pinfunction "VDD_1-VDD") (pintype "power_in"))
      (node (ref "LED19") (pin "1-VDD") (pinfunction "VDD_1-VDD") (pintype "power_in"))
      (node (ref "LED2") (pin "1-VDD") (pinfunction "VDD_1-VDD") (pintype "power_in"))
      (node (ref "LED20") (pin "1-VDD") (pinfunction "VDD_1-VDD") (pintype "power_in"))
      (node (ref "LED21") (pin "1-VDD") (pinfunction "VDD_1-VDD") (pintype "power_in"))
      (node (ref "LED22") (pin "1-VDD") (pinfunction "VDD_1-VDD") (pintype "power_in"))
      (node (ref "LED23") (pin "1-VDD") (pinfunction "VDD_1-VDD") (pintype "power_in"))
      (node (ref "LED24") (pin "1-VDD") (pinfunction "VDD_1-VDD") (pintype "power_in"))
      (node (ref "LED25") (pin "1-VDD") (pinfunction "VDD_1-VDD") (pintype "power_in"))
      (node (ref "LED26") (pin "1-VDD") (pinfunction "VDD_1-VDD") (pintype "power_in"))
      (node (ref "LED27") (pin "1-VDD") (pinfunction "VDD_1-VDD") (pintype "power_in"))
      (node (ref "LED28") (pin "1-VDD") (pinfunction "VDD_1-VDD") (pintype "power_in"))
      (node (ref "LED29") (pin "1-VDD") (pinfunction "VDD_1-VDD") (pintype "power_in"))
      (node (ref "LED3") (pin "1-VDD") (pinfunction "VDD_1-VDD") (pintype "power_in"))
      (node (ref "LED30") (pin "1-VDD") (pinfunction "VDD_1-VDD") (pintype "power_in"))
      (node (ref "LED31") (pin "1-VDD") (pinfunction "VDD_1-VDD") (pintype "power_in"))
      (node (ref "LED32") (pin "1-VDD") (pinfunction "VDD_1-VDD") (pintype "power_in"))
      (node (ref "LED33") (pin "1-VDD") (pinfunction "VDD_1-VDD") (pintype "power_in"))
      (node (ref "LED34") (pin "1-VDD") (pinfunction "VDD_1-VDD") (pintype "power_in"))
      (node (ref "LED35") (pin "1-VDD") (pinfunction "VDD_1-VDD") (pintype "power_in"))
      (node (ref "LED36") (pin "1-VDD") (pinfunction "VDD_1-VDD") (pintype "power_in"))
      (node (ref "LED37") (pin "1-VDD") (pinfunction "VDD_1-VDD") (pintype "power_in"))
      (node (ref "LED38") (pin "1-VDD") (pinfunction "VDD_1-VDD") (pintype "power_in"))
      (node (ref "LED39") (pin "1-VDD") (pinfunction "VDD_1-VDD") (pintype "power_in"))
      (node (ref "LED4") (pin "1-VDD") (pinfunction "VDD_1-VDD") (pintype "power_in"))
      (node (ref "LED40") (pin "1-VDD") (pinfunction "VDD_1-VDD") (pintype "power_in"))
      (node (ref "LED5") (pin "1-VDD") (pinfunction "VDD_1-VDD") (pintype "power_in"))
      (node (ref "LED6") (pin "1-VDD") (pinfunction "VDD_1-VDD") (pintype "power_in"))
      (node (ref "LED7") (pin "1-VDD") (pinfunction "VDD_1-VDD") (pintype "power_in"))
      (node (ref "LED8") (pin "1-VDD") (pinfunction "VDD_1-VDD") (pintype "power_in"))
      (node (ref "LED9") (pin "1-VDD") (pinfunction "VDD_1-VDD") (pintype "power_in"))
      (node (ref "R15") (pin "2") (pinfunction "2_2") (pintype "passive"))
      (node (ref "U1") (pin "P$36") (pinfunction "3V3(OUT)_P$36") (pintype "power_in"))
    )
    (net (code "2") (name "COL1") (class "Default")
      (node (ref "K1") (pin "T1") (pinfunction "T1_T1") (pintype "bidirectional"))
      (node (ref "K11") (pin "T1") (pinfunction "T1_T1") (pintype "bidirectional"))
      (node (ref "K21") (pin "T1") (pinfunction "T1_T1") (pintype "bidirectional"))
      (node (ref "K31") (pin "T1") (pinfunction "T1_T1") (pintype "bidirectional"))
      (node (ref "R1") (pin "2") (pinfunction "2_2") (pintype "passive"))
      (node (ref "U1") (pin "P$1") (pinfunction "GP0_P$1") (pintype "bidirectional"))
    )
    (net (code "3") (name "COL2") (class "Default")
      (node (ref "K12") (pin "T1") (pinfunction "T1_T1") (pintype "bidirectional"))
      (node (ref "K2") (pin "T1") (pinfunction "T1_T1") (pintype "bidirectional"))
      (node (ref "K22") (pin "T1") (pinfunction "T1_T1") (pintype "bidirectional"))
      (node (ref "K32") (pin "T1") (pinfunction "T1_T1") (pintype "bidirectional"))
      (node (ref "R2") (pin "2") (pinfunction "2_2") (pintype "passive"))
      (node (ref "U1") (pin "P$2") (pinfunction "GP1_P$2") (pintype "bidirectional"))
    )
    (net (code "4") (name "COL3") (class "Default")
      (node (ref "K13") (pin "T1") (pinfunction "T1_T1") (pintype "bidirectional"))
      (node (ref "K23") (pin "T1") (pinfunction "T1_T1") (pintype "bidirectional"))
      (node (ref "K3") (pin "T1") (pinfunction "T1_T1") (pintype "bidirectional"))
      (node (ref "K33") (pin "T1") (pinfunction "T1_T1") (pintype "bidirectional"))
      (node (ref "R3") (pin "2") (pinfunction "2_2") (pintype "passive"))
      (node (ref "U1") (pin "P$4") (pinfunction "GP2_P$4") (pintype "bidirectional"))
    )
    (net (code "5") (name "COL4") (class "Default")
      (node (ref "K14") (pin "T1") (pinfunction "T1_T1") (pintype "bidirectional"))
      (node (ref "K24") (pin "T1") (pinfunction "T1_T1") (pintype "bidirectional"))
      (node (ref "K34") (pin "T1") (pinfunction "T1_T1") (pintype "bidirectional"))
      (node (ref "K4") (pin "T1") (pinfunction "T1_T1") (pintype "bidirectional"))
      (node (ref "R4") (pin "2") (pinfunction "2_2") (pintype "passive"))
      (node (ref "U1") (pin "P$5") (pinfunction "GP3_P$5") (pintype "bidirectional"))
    )
    (net (code "6") (name "COL5") (class "Default")
      (node (ref "K15") (pin "T1") (pinfunction "T1_T1") (pintype "bidirectional"))
      (node (ref "K25") (pin "T1") (pinfunction "T1_T1") (pintype "bidirectional"))
      (node (ref "K35") (pin "T1") (pinfunction "T1_T1") (pintype "bidirectional"))
      (node (ref "K5") (pin "T1") (pinfunction "T1_T1") (pintype "bidirectional"))
      (node (ref "R5") (pin "2") (pinfunction "2_2") (pintype "passive"))
      (node (ref "U1") (pin "P$6") (pinfunction "GP4_P$6") (pintype "bidirectional"))
    )
    (net (code "7") (name "COL6") (class "Default")
      (node (ref "K16") (pin "T1") (pinfunction "T1_T1") (pintype "bidirectional"))
      (node (ref "K26") (pin "T1") (pinfunction "T1_T1") (pintype "bidirectional"))
      (node (ref "K36") (pin "T1") (pinfunction "T1_T1") (pintype "bidirectional"))
      (node (ref "K6") (pin "T1") (pinfunction "T1_T1") (pintype "bidirectional"))
      (node (ref "R6") (pin "2") (pinfunction "2_2") (pintype "passive"))
      (node (ref "U1") (pin "P$7") (pinfunction "GP5_P$7") (pintype "bidirectional"))
    )
    (net (code "8") (name "COL7") (class "Default")
      (node (ref "K17") (pin "T1") (pinfunction "T1_T1") (pintype "bidirectional"))
      (node (ref "K27") (pin "T1") (pinfunction "T1_T1") (pintype "bidirectional"))
      (node (ref "K37") (pin "T1") (pinfunction "T1_T1") (pintype "bidirectional"))
      (node (ref "K7") (pin "T1") (pinfunction "T1_T1") (pintype "bidirectional"))
      (node (ref "R7") (pin "2") (pinfunction "2_2") (pintype "passive"))
      (node (ref "U1") (pin "P$9") (pinfunction "GP6_P$9") (pintype "bidirectional"))
    )
    (net (code "9") (name "COL8") (class "Default")
      (node (ref "K18") (pin "T1") (pinfunction "T1_T1") (pintype "bidirectional"))
      (node (ref "K28") (pin "T1") (pinfunction "T1_T1") (pintype "bidirectional"))
      (node (ref "K38") (pin "T1") (pinfunction "T1_T1") (pintype "bidirectional"))
      (node (ref "K8") (pin "T1") (pinfunction "T1_T1") (pintype "bidirectional"))
      (node (ref "R8") (pin "2") (pinfunction "2_2") (pintype "passive"))
      (node (ref "U1") (pin "P$10") (pinfunction "GP7_P$10") (pintype "bidirectional"))
    )
    (net (code "10") (name "COL9") (class "Default")
      (node (ref "K19") (pin "T1") (pinfunction "T1_T1") (pintype "bidirectional"))
      (node (ref "K29") (pin "T1") (pinfunction "T1_T1") (pintype "bidirectional"))
      (node (ref "K39") (pin "T1") (pinfunction "T1_T1") (pintype "bidirectional"))
      (node (ref "K9") (pin "T1") (pinfunction "T1_T1") (pintype "bidirectional"))
      (node (ref "R9") (pin "2") (pinfunction "2_2") (pintype "passive"))
      (node (ref "U1") (pin "P$11") (pinfunction "GP8_P$11") (pintype "bidirectional"))
    )
    (net (code "11") (name "COL10") (class "Default")
      (node (ref "K10") (pin "T1") (pinfunction "T1_T1") (pintype "bidirectional"))
      (node (ref "K20") (pin "T1") (pinfunction "T1_T1") (pintype "bidirectional"))
      (node (ref "K30") (pin "T1") (pinfunction "T1_T1") (pintype "bidirectional"))
      (node (ref "K40") (pin "T1") (pinfunction "T1_T1") (pintype "bidirectional"))
      (node (ref "R10") (pin "2") (pinfunction "2_2") (pintype "passive"))
      (node (ref "U1") (pin "P$12") (pinfunction "GP9_P$12") (pintype "bidirectional"))
    )
    (net (code "12") (name "GND") (class "Default")
      (node (ref "C1") (pin "2") (pinfunction "2_2") (pintype "passive"))
      (node (ref "C10") (pin "2") (pinfunction "2_2") (pintype "passive"))
      (node (ref "C11") (pin "2") (pinfunction "2_2") (pintype "passive"))
      (node (ref "C12") (pin "2") (pinfunction "2_2") (pintype "passive"))
      (node (ref "C13") (pin "2") (pinfunction "2_2") (pintype "passive"))
      (node (ref "C14") (pin "2") (pinfunction "2_2") (pintype "passive"))
      (node (ref "C15") (pin "2") (pinfunction "2_2") (pintype "passive"))
      (node (ref "C16") (pin "2") (pinfunction "2_2") (pintype "passive"))
      (node (ref "C17") (pin "2") (pinfunction "2_2") (pintype "passive"))
      (node (ref "C18") (pin "2") (pinfunction "2_2") (pintype "passive"))
      (node (ref "C19") (pin "2") (pinfunction "2_2") (pintype "passive"))
      (node (ref "C2") (pin "2") (pinfunction "2_2") (pintype "passive"))
      (node (ref "C20") (pin "2") (pinfunction "2_2") (pintype "passive"))
      (node (ref "C21") (pin "2") (pinfunction "2_2") (pintype "passive"))
      (node (ref "C22") (pin "2") (pinfunction "2_2") (pintype "passive"))
      (node (ref "C23") (pin "2") (pinfunction "2_2") (pintype "passive"))
      (node (ref "C24") (pin "2") (pinfunction "2_2") (pintype "passive"))
      (node (ref "C25") (pin "2") (pinfunction "2_2") (pintype "passive"))
      (node (ref "C26") (pin "2") (pinfunction "2_2") (pintype "passive"))
      (node (ref "C27") (pin "2") (pinfunction "2_2") (pintype "passive"))
      (node (ref "C28") (pin "2") (pinfunction "2_2") (pintype "passive"))
      (node (ref "C29") (pin "2") (pinfunction "2_2") (pintype "passive"))
      (node (ref "C3") (pin "2") (pinfunction "2_2") (pintype "passive"))
      (node (ref "C30") (pin "2") (pinfunction "2_2") (pintype "passive"))
      (node (ref "C31") (pin "2") (pinfunction "2_2") (pintype "passive"))
      (node (ref "C32") (pin "2") (pinfunction "2_2") (pintype "passive"))
      (node (ref "C33") (pin "2") (pinfunction "2_2") (pintype "passive"))
      (node (ref "C34") (pin "2") (pinfunction "2_2") (pintype "passive"))
      (node (ref "C35") (pin "2") (pinfunction "2_2") (pintype "passive"))
      (node (ref "C36") (pin "2") (pinfunction "2_2") (pintype "passive"))
      (node (ref "C37") (pin "2") (pinfunction "2_2") (pintype "passive"))
      (node (ref "C38") (pin "2") (pinfunction "2_2") (pintype "passive"))
      (node (ref "C39") (pin "2") (pinfunction "2_2") (pintype "passive"))
      (node (ref "C4") (pin "2") (pinfunction "2_2") (pintype "passive"))
      (node (ref "C40") (pin "2") (pinfunction "2_2") (pintype "passive"))
      (node (ref "C5") (pin "2") (pinfunction "2_2") (pintype "passive"))
      (node (ref "C6") (pin "2") (pinfunction "2_2") (pintype "passive"))
      (node (ref "C7") (pin "2") (pinfunction "2_2") (pintype "passive"))
      (node (ref "C8") (pin "2") (pinfunction "2_2") (pintype "passive"))
      (node (ref "C9") (pin "2") (pinfunction "2_2") (pintype "passive"))
      (node (ref "CONN1") (pin "1") (pinfunction "GND_1") (pintype "passive"))
      (node (ref "CONN1") (pin "MT1") (pinfunction "MT_MT1") (pintype "bidirectional"))
      (node (ref "CONN1") (pin "MT2") (pinfunction "MT_MT2") (pintype "bidirectional"))
      (node (ref "J1") (pin "1") (pinfunction "1_1") (pintype "passive"))
      (node (ref "J3") (pin "EARTH") (pinfunction "EARTH_EARTH") (pintype "bidirectional"))
      (node (ref "LED1") (pin "3-GND") (pinfunction "GND_3-GND") (pintype "power_in"))
      (node (ref "LED10") (pin "3-GND") (pinfunction "GND_3-GND") (pintype "power_in"))
      (node (ref "LED11") (pin "3-GND") (pinfunction "GND_3-GND") (pintype "power_in"))
      (node (ref "LED12") (pin "3-GND") (pinfunction "GND_3-GND") (pintype "power_in"))
      (node (ref "LED13") (pin "3-GND") (pinfunction "GND_3-GND") (pintype "power_in"))
      (node (ref "LED14") (pin "3-GND") (pinfunction "GND_3-GND") (pintype "power_in"))
      (node (ref "LED15") (pin "3-GND") (pinfunction "GND_3-GND") (pintype "power_in"))
      (node (ref "LED16") (pin "3-GND") (pinfunction "GND_3-GND") (pintype "power_in"))
      (node (ref "LED17") (pin "3-GND") (pinfunction "GND_3-GND") (pintype "power_in"))
      (node (ref "LED18") (pin "3-GND") (pinfunction "GND_3-GND") (pintype "power_in"))
      (node (ref "LED19") (pin "3-GND") (pinfunction "GND_3-GND") (pintype "power_in"))
      (node (ref "LED2") (pin "3-GND") (pinfunction "GND_3-GND") (pintype "power_in"))
      (node (ref "LED20") (pin "3-GND") (pinfunction "GND_3-GND") (pintype "power_in"))
      (node (ref "LED21") (pin "3-GND") (pinfunction "GND_3-GND") (pintype "power_in"))
      (node (ref "LED22") (pin "3-GND") (pinfunction "GND_3-GND") (pintype "power_in"))
      (node (ref "LED23") (pin "3-GND") (pinfunction "GND_3-GND") (pintype "power_in"))
      (node (ref "LED24") (pin "3-GND") (pinfunction "GND_3-GND") (pintype "power_in"))
      (node (ref "LED25") (pin "3-GND") (pinfunction "GND_3-GND") (pintype "power_in"))
      (node (ref "LED26") (pin "3-GND") (pinfunction "GND_3-GND") (pintype "power_in"))
      (node (ref "LED27") (pin "3-GND") (pinfunction "GND_3-GND") (pintype "power_in"))
      (node (ref "LED28") (pin "3-GND") (pinfunction "GND_3-GND") (pintype "power_in"))
      (node (ref "LED29") (pin "3-GND") (pinfunction "GND_3-GND") (pintype "power_in"))
      (node (ref "LED3") (pin "3-GND") (pinfunction "GND_3-GND") (pintype "power_in"))
      (node (ref "LED30") (pin "3-GND") (pinfunction "GND_3-GND") (pintype "power_in"))
      (node (ref "LED31") (pin "3-GND") (pinfunction "GND_3-GND") (pintype "power_in"))
      (node (ref "LED32") (pin "3-GND") (pinfunction "GND_3-GND") (pintype "power_in"))
      (node (ref "LED33") (pin "3-GND") (pinfunction "GND_3-GND") (pintype "power_in"))
      (node (ref "LED34") (pin "3-GND") (pinfunction "GND_3-GND") (pintype "power_in"))
      (node (ref "LED35") (pin "3-GND") (pinfunction "GND_3-GND") (pintype "power_in"))
      (node (ref "LED36") (pin "3-GND") (pinfunction "GND_3-GND") (pintype "power_in"))
      (node (ref "LED37") (pin "3-GND") (pinfunction "GND_3-GND") (pintype "power_in"))
      (node (ref "LED38") (pin "3-GND") (pinfunction "GND_3-GND") (pintype "power_in"))
      (node (ref "LED39") (pin "3-GND") (pinfunction "GND_3-GND") (pintype "power_in"))
      (node (ref "LED4") (pin "3-GND") (pinfunction "GND_3-GND") (pintype "power_in"))
      (node (ref "LED40") (pin "3-GND") (pinfunction "GND_3-GND") (pintype "power_in"))
      (node (ref "LED5") (pin "3-GND") (pinfunction "GND_3-GND") (pintype "power_in"))
      (node (ref "LED6") (pin "3-GND") (pinfunction "GND_3-GND") (pintype "power_in"))
      (node (ref "LED7") (pin "3-GND") (pinfunction "GND_3-GND") (pintype "power_in"))
      (node (ref "LED8") (pin "3-GND") (pinfunction "GND_3-GND") (pintype "power_in"))
      (node (ref "LED9") (pin "3-GND") (pinfunction "GND_3-GND") (pintype "power_in"))
      (node (ref "R1") (pin "1") (pinfunction "1_1") (pintype "passive"))
      (node (ref "R10") (pin "1") (pinfunction "1_1") (pintype "passive"))
      (node (ref "R11") (pin "1") (pinfunction "1_1") (pintype "passive"))
      (node (ref "R12") (pin "1") (pinfunction "1_1") (pintype "passive"))
      (node (ref "R13") (pin "1") (pinfunction "1_1") (pintype "passive"))
      (node (ref "R14") (pin "1") (pinfunction "1_1") (pintype "passive"))
      (node (ref "R2") (pin "1") (pinfunction "1_1") (pintype "passive"))
      (node (ref "R3") (pin "1") (pinfunction "1_1") (pintype "passive"))
      (node (ref "R4") (pin "1") (pinfunction "1_1") (pintype "passive"))
      (node (ref "R5") (pin "1") (pinfunction "1_1") (pintype "passive"))
      (node (ref "R6") (pin "1") (pinfunction "1_1") (pintype "passive"))
      (node (ref "R7") (pin "1") (pinfunction "1_1") (pintype "passive"))
      (node (ref "R8") (pin "1") (pinfunction "1_1") (pintype "passive"))
      (node (ref "R9") (pin "1") (pinfunction "1_1") (pintype "passive"))
      (node (ref "U1") (pin "P$13") (pinfunction "GND_P$13") (pintype "power_in"))
      (node (ref "U1") (pin "P$18") (pinfunction "GND_P$18") (pintype "power_in"))
      (node (ref "U1") (pin "P$23") (pinfunction "GND_P$23") (pintype "power_in"))
      (node (ref "U1") (pin "P$28") (pinfunction "GND_P$28") (pintype "power_in"))
      (node (ref "U1") (pin "P$3") (pinfunction "GND_P$3") (pintype "power_in"))
      (node (ref "U1") (pin "P$33") (pinfunction "GND_P$33") (pintype "power_in"))
      (node (ref "U1") (pin "P$38") (pinfunction "GND_P$38") (pintype "power_in"))
      (node (ref "U1") (pin "P$8") (pinfunction "GND_P$8") (pintype "power_in"))
    )
    (net (code "13") (name "MIDI_OUT") (class "Default")
      (node (ref "R16") (pin "2") (pinfunction "2_2") (pintype "passive"))
      (node (ref "U1") (pin "P$26") (pinfunction "GP20_P$26") (pintype "bidirectional"))
    )
    (net (code "14") (name "NEOPIXEL") (class "Default")
      (node (ref "LED1") (pin "4-DIN") (pinfunction "DI_4-DIN") (pintype "input"))
      (node (ref "U1") (pin "P$34") (pinfunction "GP28_P$34") (pintype "bidirectional"))
    )
    (net (code "15") (name "Net-(J3-PadRING1)") (class "Default")
      (node (ref "J3") (pin "RING1") (pinfunction "RING1_RING1") (pintype "bidirectional"))
      (node (ref "R15") (pin "1") (pinfunction "1_1") (pintype "passive"))
    )
    (net (code "16") (name "Net-(J3-PadTIP)") (class "Default")
      (node (ref "J3") (pin "TIP") (pinfunction "TIP_TIP") (pintype "bidirectional"))
      (node (ref "R16") (pin "1") (pinfunction "1_1") (pintype "passive"))
    )
    (net (code "17") (name "Net-(LED1-DO)") (class "Default")
      (node (ref "LED1") (pin "2-DOUT") (pinfunction "DO_2-DOUT") (pintype "output"))
      (node (ref "LED2") (pin "4-DIN") (pinfunction "DI_4-DIN") (pintype "input"))
    )
    (net (code "18") (name "Net-(LED2-DO)") (class "Default")
      (node (ref "LED2") (pin "2-DOUT") (pinfunction "DO_2-DOUT") (pintype "output"))
      (node (ref "LED3") (pin "4-DIN") (pinfunction "DI_4-DIN") (pintype "input"))
    )
    (net (code "19") (name "Net-(LED3-DO)") (class "Default")
      (node (ref "LED3") (pin "2-DOUT") (pinfunction "DO_2-DOUT") (pintype "output"))
      (node (ref "LED4") (pin "4-DIN") (pinfunction "DI_4-DIN") (pintype "input"))
    )
    (net (code "20") (name "Net-(LED4-DO)") (class "Default")
      (node (ref "LED4") (pin "2-DOUT") (pinfunction "DO_2-DOUT") (pintype "output"))
      (node (ref "LED5") (pin "4-DIN") (pinfunction "DI_4-DIN") (pintype "input"))
    )
    (net (code "21") (name "Net-(LED5-DO)") (class "Default")
      (node (ref "LED5") (pin "2-DOUT") (pinfunction "DO_2-DOUT") (pintype "output"))
      (node (ref "LED6") (pin "4-DIN") (pinfunction "DI_4-DIN") (pintype "input"))
    )
    (net (code "22") (name "Net-(LED6-DO)") (class "Default")
      (node (ref "LED6") (pin "2-DOUT") (pinfunction "DO_2-DOUT") (pintype "output"))
      (node (ref "LED7") (pin "4-DIN") (pinfunction "DI_4-DIN") (pintype "input"))
    )
    (net (code "23") (name "Net-(LED7-DO)") (class "Default")
      (node (ref "LED7") (pin "2-DOUT") (pinfunction "DO_2-DOUT") (pintype "output"))
      (node (ref "LED8") (pin "4-DIN") (pinfunction "DI_4-DIN") (pintype "input"))
    )
    (net (code "24") (name "Net-(LED8-DO)") (class "Default")
      (node (ref "LED8") (pin "2-DOUT") (pinfunction "DO_2-DOUT") (pintype "output"))
      (node (ref "LED9") (pin "4-DIN") (pinfunction "DI_4-DIN") (pintype "input"))
    )
    (net (code "25") (name "Net-(LED10-DI)") (class "Default")
      (node (ref "LED10") (pin "4-DIN") (pinfunction "DI_4-DIN") (pintype "input"))
      (node (ref "LED9") (pin "2-DOUT") (pinfunction "DO_2-DOUT") (pintype "output"))
    )
    (net (code "26") (name "Net-(LED10-DO)") (class "Default")
      (node (ref "LED10") (pin "2-DOUT") (pinfunction "DO_2-DOUT") (pintype "output"))
      (node (ref "LED11") (pin "4-DIN") (pinfunction "DI_4-DIN") (pintype "input"))
    )
    (net (code "27") (name "Net-(LED11-DO)") (class "Default")
      (node (ref "LED11") (pin "2-DOUT") (pinfunction "DO_2-DOUT") (pintype "output"))
      (node (ref "LED12") (pin "4-DIN") (pinfunction "DI_4-DIN") (pintype "input"))
    )
    (net (code "28") (name "Net-(LED12-DO)") (class "Default")
      (node (ref "LED12") (pin "2-DOUT") (pinfunction "DO_2-DOUT") (pintype "output"))
      (node (ref "LED13") (pin "4-DIN") (pinfunction "DI_4-DIN") (pintype "input"))
    )
    (net (code "29") (name "Net-(LED13-DO)") (class "Default")
      (node (ref "LED13") (pin "2-DOUT") (pinfunction "DO_2-DOUT") (pintype "output"))
      (node (ref "LED14") (pin "4-DIN") (pinfunction "DI_4-DIN") (pintype "input"))
    )
    (net (code "30") (name "Net-(LED14-DO)") (class "Default")
      (node (ref "LED14") (pin "2-DOUT") (pinfunction "DO_2-DOUT") (pintype "output"))
      (node (ref "LED15") (pin "4-DIN") (pinfunction "DI_4-DIN") (pintype "input"))
    )
    (net (code "31") (name "Net-(LED15-DO)") (class "Default")
      (node (ref "LED15") (pin "2-DOUT") (pinfunction "DO_2-DOUT") (pintype "output"))
      (node (ref "LED16") (pin "4-DIN") (pinfunction "DI_4-DIN") (pintype "input"))
    )
    (net (code "32") (name "Net-(LED16-DO)") (class "Default")
      (node (ref "LED16") (pin "2-DOUT") (pinfunction "DO_2-DOUT") (pintype "output"))
      (node (ref "LED17") (pin "4-DIN") (pinfunction "DI_4-DIN") (pintype "input"))
    )
    (net (code "33") (name "Net-(LED17-DO)") (class "Default")
      (node (ref "LED17") (pin "2-DOUT") (pinfunction "DO_2-DOUT") (pintype "output"))
      (node (ref "LED18") (pin "4-DIN") (pinfunction "DI_4-DIN") (pintype "input"))
    )
    (net (code "34") (name "Net-(LED18-DO)") (class "Default")
      (node (ref "LED18") (pin "2-DOUT") (pinfunction "DO_2-DOUT") (pintype "output"))
      (node (ref "LED19") (pin "4-DIN") (pinfunction "DI_4-DIN") (pintype "input"))
    )
    (net (code "35") (name "Net-(LED19-DO)") (class "Default")
      (node (ref "LED19") (pin "2-DOUT") (pinfunction "DO_2-DOUT") (pintype "output"))
      (node (ref "LED20") (pin "4-DIN") (pinfunction "DI_4-DIN") (pintype "input"))
    )
    (net (code "36") (name "Net-(LED20-DO)") (class "Default")
      (node (ref "LED20") (pin "2-DOUT") (pinfunction "DO_2-DOUT") (pintype "output"))
      (node (ref "LED21") (pin "4-DIN") (pinfunction "DI_4-DIN") (pintype "input"))
    )
    (net (code "37") (name "Net-(LED21-DO)") (class "Default")
      (node (ref "LED21") (pin "2-DOUT") (pinfunction "DO_2-DOUT") (pintype "output"))
      (node (ref "LED22") (pin "4-DIN") (pinfunction "DI_4-DIN") (pintype "input"))
    )
    (net (code "38") (name "Net-(LED22-DO)") (class "Default")
      (node (ref "LED22") (pin "2-DOUT") (pinfunction "DO_2-DOUT") (pintype "output"))
      (node (ref "LED23") (pin "4-DIN") (pinfunction "DI_4-DIN") (pintype "input"))
    )
    (net (code "39") (name "Net-(LED23-DO)") (class "Default")
      (node (ref "LED23") (pin "2-DOUT") (pinfunction "DO_2-DOUT") (pintype "output"))
      (node (ref "LED24") (pin "4-DIN") (pinfunction "DI_4-DIN") (pintype "input"))
    )
    (net (code "40") (name "Net-(LED24-DO)") (class "Default")
      (node (ref "LED24") (pin "2-DOUT") (pinfunction "DO_2-DOUT") (pintype "output"))
      (node (ref "LED25") (pin "4-DIN") (pinfunction "DI_4-DIN") (pintype "input"))
    )
    (net (code "41") (name "Net-(LED25-DO)") (class "Default")
      (node (ref "LED25") (pin "2-DOUT") (pinfunction "DO_2-DOUT") (pintype "output"))
      (node (ref "LED26") (pin "4-DIN") (pinfunction "DI_4-DIN") (pintype "input"))
    )
    (net (code "42") (name "Net-(LED26-DO)") (class "Default")
      (node (ref "LED26") (pin "2-DOUT") (pinfunction "DO_2-DOUT") (pintype "output"))
      (node (ref "LED27") (pin "4-DIN") (pinfunction "DI_4-DIN") (pintype "input"))
    )
    (net (code "43") (name "Net-(LED27-DO)") (class "Default")
      (node (ref "LED27") (pin "2-DOUT") (pinfunction "DO_2-DOUT") (pintype "output"))
      (node (ref "LED28") (pin "4-DIN") (pinfunction "DI_4-DIN") (pintype "input"))
    )
    (net (code "44") (name "Net-(LED28-DO)") (class "Default")
      (node (ref "LED28") (pin "2-DOUT") (pinfunction "DO_2-DOUT") (pintype "output"))
      (node (ref "LED29") (pin "4-DIN") (pinfunction "DI_4-DIN") (pintype "input"))
    )
    (net (code "45") (name "Net-(LED29-DO)") (class "Default")
      (node (ref "LED29") (pin "2-DOUT") (pinfunction "DO_2-DOUT") (pintype "output"))
      (node (ref "LED30") (pin "4-DIN") (pinfunction "DI_4-DIN") (pintype "input"))
    )
    (net (code "46") (name "Net-(LED30-DO)") (class "Default")
      (node (ref "LED30") (pin "2-DOUT") (pinfunction "DO_2-DOUT") (pintype "output"))
      (node (ref "LED31") (pin "4-DIN") (pinfunction "DI_4-DIN") (pintype "input"))
    )
    (net (code "47") (name "Net-(LED31-DO)") (class "Default")
      (node (ref "LED31") (pin "2-DOUT") (pinfunction "DO_2-DOUT") (pintype "output"))
      (node (ref "LED32") (pin "4-DIN") (pinfunction "DI_4-DIN") (pintype "input"))
    )
    (net (code "48") (name "Net-(LED32-DO)") (class "Default")
      (node (ref "LED32") (pin "2-DOUT") (pinfunction "DO_2-DOUT") (pintype "output"))
      (node (ref "LED33") (pin "4-DIN") (pinfunction "DI_4-DIN") (pintype "input"))
    )
    (net (code "49") (name "Net-(LED33-DO)") (class "Default")
      (node (ref "LED33") (pin "2-DOUT") (pinfunction "DO_2-DOUT") (pintype "output"))
      (node (ref "LED34") (pin "4-DIN") (pinfunction "DI_4-DIN") (pintype "input"))
    )
    (net (code "50") (name "Net-(LED34-DO)") (class "Default")
      (node (ref "LED34") (pin "2-DOUT") (pinfunction "DO_2-DOUT") (pintype "output"))
      (node (ref "LED35") (pin "4-DIN") (pinfunction "DI_4-DIN") (pintype "input"))
    )
    (net (code "51") (name "Net-(LED35-DO)") (class "Default")
      (node (ref "LED35") (pin "2-DOUT") (pinfunction "DO_2-DOUT") (pintype "output"))
      (node (ref "LED36") (pin "4-DIN") (pinfunction "DI_4-DIN") (pintype "input"))
    )
    (net (code "52") (name "Net-(LED36-DO)") (class "Default")
      (node (ref "LED36") (pin "2-DOUT") (pinfunction "DO_2-DOUT") (pintype "output"))
      (node (ref "LED37") (pin "4-DIN") (pinfunction "DI_4-DIN") (pintype "input"))
    )
    (net (code "53") (name "Net-(LED37-DO)") (class "Default")
      (node (ref "LED37") (pin "2-DOUT") (pinfunction "DO_2-DOUT") (pintype "output"))
      (node (ref "LED38") (pin "4-DIN") (pinfunction "DI_4-DIN") (pintype "input"))
    )
    (net (code "54") (name "Net-(LED38-DO)") (class "Default")
      (node (ref "LED38") (pin "2-DOUT") (pinfunction "DO_2-DOUT") (pintype "output"))
      (node (ref "LED39") (pin "4-DIN") (pinfunction "DI_4-DIN") (pintype "input"))
    )
    (net (code "55") (name "Net-(LED39-DO)") (class "Default")
      (node (ref "LED39") (pin "2-DOUT") (pinfunction "DO_2-DOUT") (pintype "output"))
      (node (ref "LED40") (pin "4-DIN") (pinfunction "DI_4-DIN") (pintype "input"))
    )
    (net (code "56") (name "ROW1") (class "Default")
      (node (ref "K1") (pin "T2") (pinfunction "T2_T2") (pintype "bidirectional"))
      (node (ref "K10") (pin "T2") (pinfunction "T2_T2") (pintype "bidirectional"))
      (node (ref "K2") (pin "T2") (pinfunction "T2_T2") (pintype "bidirectional"))
      (node (ref "K3") (pin "T2") (pinfunction "T2_T2") (pintype "bidirectional"))
      (node (ref "K4") (pin "T2") (pinfunction "T2_T2") (pintype "bidirectional"))
      (node (ref "K5") (pin "T2") (pinfunction "T2_T2") (pintype "bidirectional"))
      (node (ref "K6") (pin "T2") (pinfunction "T2_T2") (pintype "bidirectional"))
      (node (ref "K7") (pin "T2") (pinfunction "T2_T2") (pintype "bidirectional"))
      (node (ref "K8") (pin "T2") (pinfunction "T2_T2") (pintype "bidirectional"))
      (node (ref "K9") (pin "T2") (pinfunction "T2_T2") (pintype "bidirectional"))
      (node (ref "R11") (pin "2") (pinfunction "2_2") (pintype "passive"))
      (node (ref "U1") (pin "P$14") (pinfunction "GP10_P$14") (pintype "bidirectional"))
    )
    (net (code "57") (name "ROW2") (class "Default")
      (node (ref "K11") (pin "T2") (pinfunction "T2_T2") (pintype "bidirectional"))
      (node (ref "K12") (pin "T2") (pinfunction "T2_T2") (pintype "bidirectional"))
      (node (ref "K13") (pin "T2") (pinfunction "T2_T2") (pintype "bidirectional"))
      (node (ref "K14") (pin "T2") (pinfunction "T2_T2") (pintype "bidirectional"))
      (node (ref "K15") (pin "T2") (pinfunction "T2_T2") (pintype "bidirectional"))
      (node (ref "K16") (pin "T2") (pinfunction "T2_T2") (pintype "bidirectional"))
      (node (ref "K17") (pin "T2") (pinfunction "T2_T2") (pintype "bidirectional"))
      (node (ref "K18") (pin "T2") (pinfunction "T2_T2") (pintype "bidirectional"))
      (node (ref "K19") (pin "T2") (pinfunction "T2_T2") (pintype "bidirectional"))
      (node (ref "K20") (pin "T2") (pinfunction "T2_T2") (pintype "bidirectional"))
      (node (ref "R12") (pin "2") (pinfunction "2_2") (pintype "passive"))
      (node (ref "U1") (pin "P$15") (pinfunction "GP11_P$15") (pintype "bidirectional"))
    )
    (net (code "58") (name "ROW3") (class "Default")
      (node (ref "K21") (pin "T2") (pinfunction "T2_T2") (pintype "bidirectional"))
      (node (ref "K22") (pin "T2") (pinfunction "T2_T2") (pintype "bidirectional"))
      (node (ref "K23") (pin "T2") (pinfunction "T2_T2") (pintype "bidirectional"))
      (node (ref "K24") (pin "T2") (pinfunction "T2_T2") (pintype "bidirectional"))
      (node (ref "K25") (pin "T2") (pinfunction "T2_T2") (pintype "bidirectional"))
      (node (ref "K26") (pin "T2") (pinfunction "T2_T2") (pintype "bidirectional"))
      (node (ref "K27") (pin "T2") (pinfunction "T2_T2") (pintype "bidirectional"))
      (node (ref "K28") (pin "T2") (pinfunction "T2_T2") (pintype "bidirectional"))
      (node (ref "K29") (pin "T2") (pinfunction "T2_T2") (pintype "bidirectional"))
      (node (ref "K30") (pin "T2") (pinfunction "T2_T2") (pintype "bidirectional"))
      (node (ref "R13") (pin "2") (pinfunction "2_2") (pintype "passive"))
      (node (ref "U1") (pin "P$16") (pinfunction "GP12_P$16") (pintype "bidirectional"))
    )
    (net (code "59") (name "ROW4") (class "Default")
      (node (ref "K31") (pin "T2") (pinfunction "T2_T2") (pintype "bidirectional"))
      (node (ref "K32") (pin "T2") (pinfunction "T2_T2") (pintype "bidirectional"))
      (node (ref "K33") (pin "T2") (pinfunction "T2_T2") (pintype "bidirectional"))
      (node (ref "K34") (pin "T2") (pinfunction "T2_T2") (pintype "bidirectional"))
      (node (ref "K35") (pin "T2") (pinfunction "T2_T2") (pintype "bidirectional"))
      (node (ref "K36") (pin "T2") (pinfunction "T2_T2") (pintype "bidirectional"))
      (node (ref "K37") (pin "T2") (pinfunction "T2_T2") (pintype "bidirectional"))
      (node (ref "K38") (pin "T2") (pinfunction "T2_T2") (pintype "bidirectional"))
      (node (ref "K39") (pin "T2") (pinfunction "T2_T2") (pintype "bidirectional"))
      (node (ref "K40") (pin "T2") (pinfunction "T2_T2") (pintype "bidirectional"))
      (node (ref "R14") (pin "2") (pinfunction "2_2") (pintype "passive"))
      (node (ref "U1") (pin "P$17") (pinfunction "GP13_P$17") (pintype "bidirectional"))
    )
    (net (code "60") (name "SCL") (class "Default")
      (node (ref "CONN1") (pin "4") (pinfunction "SCL_4") (pintype "passive"))
      (node (ref "J1") (pin "3") (pinfunction "3_3") (pintype "passive"))
      (node (ref "U1") (pin "P$20") (pinfunction "GP15_P$20") (pintype "bidirectional"))
    )
    (net (code "61") (name "SDA") (class "Default")
      (node (ref "CONN1") (pin "3") (pinfunction "SDA_3") (pintype "passive"))
      (node (ref "J1") (pin "4") (pinfunction "4_4") (pintype "passive"))
      (node (ref "U1") (pin "P$19") (pinfunction "GP14_P$19") (pintype "bidirectional"))
    )
    (net (code "62") (name "SWGND") (class "Default")
      (node (ref "U1") (pin "P$42") (pinfunction "SWGND_P$42") (pintype "power_in"))
    )
    (net (code "63") (name "VBUS") (class "Default")
      (node (ref "U1") (pin "P$40") (pinfunction "VBUS_P$40") (pintype "power_in"))
    )
    (net (code "64") (name "VSYS") (class "Default")
      (node (ref "U1") (pin "P$39") (pinfunction "VSYS_P$39") (pintype "power_in"))
    )
    (net (code "65") (name "unconnected-(J3-PadRING2)") (class "Default")
      (node (ref "J3") (pin "RING2") (pinfunction "RING2_RING2") (pintype "bidirectional"))
    )
    (net (code "66") (name "unconnected-(LED40-DO-Pad2-DOUT)") (class "Default")
      (node (ref "LED40") (pin "2-DOUT") (pinfunction "DO_2-DOUT") (pintype "output"))
    )
    (net (code "67") (name "unconnected-(U1-3V3_EN-PadP$37)") (class "Default")
      (node (ref "U1") (pin "P$37") (pinfunction "3V3_EN_P$37") (pintype "input"))
    )
    (net (code "68") (name "unconnected-(U1-ADC_REF-PadP$35)") (class "Default")
      (node (ref "U1") (pin "P$35") (pinfunction "ADC_REF_P$35") (pintype "input"))
    )
    (net (code "69") (name "unconnected-(U1-GP16-PadP$21)") (class "Default")
      (node (ref "U1") (pin "P$21") (pinfunction "GP16_P$21") (pintype "bidirectional"))
    )
    (net (code "70") (name "unconnected-(U1-GP17-PadP$22)") (class "Default")
      (node (ref "U1") (pin "P$22") (pinfunction "GP17_P$22") (pintype "bidirectional"))
    )
    (net (code "71") (name "unconnected-(U1-GP18-PadP$24)") (class "Default")
      (node (ref "U1") (pin "P$24") (pinfunction "GP18_P$24") (pintype "bidirectional"))
    )
    (net (code "72") (name "unconnected-(U1-GP19-PadP$25)") (class "Default")
      (node (ref "U1") (pin "P$25") (pinfunction "GP19_P$25") (pintype "bidirectional"))
    )
    (net (code "73") (name "unconnected-(U1-GP21-PadP$27)") (class "Default")
      (node (ref "U1") (pin "P$27") (pinfunction "GP21_P$27") (pintype "bidirectional"))
    )
    (net (code "74") (name "unconnected-(U1-GP22-PadP$29)") (class "Default")
      (node (ref "U1") (pin "P$29") (pinfunction "GP22_P$29") (pintype "bidirectional"))
    )
    (net (code "75") (name "unconnected-(U1-GP26-PadP$31)") (class "Default")
      (node (ref "U1") (pin "P$31") (pinfunction "GP26_P$31") (pintype "bidirectional"))
    )
    (net (code "76") (name "unconnected-(U1-GP27-PadP$32)") (class "Default")
      (node (ref "U1") (pin "P$32") (pinfunction "GP27_P$32") (pintype "bidirectional"))
    )
    (net (code "77") (name "unconnected-(U1-RUN-PadP$30)") (class "Default")
      (node (ref "U1") (pin "P$30") (pinfunction "RUN_P$30") (pintype "input"))
    )
    (net (code "78") (name "unconnected-(U1-SWCLK-PadP$41)") (class "Default")
      (node (ref "U1") (pin "P$41") (pinfunction "SWCLK_P$41") (pintype "input"))
    )
    (net (code "79") (name "unconnected-(U1-SWDIO-PadP$43)") (class "Default")
      (node (ref "U1") (pin "P$43") (pinfunction "SWDIO_P$43") (pintype "bidirectional"))
    )
  )
)
